# LightingUPS.net
KiCad netlist of a schematic drawn in EAGLE
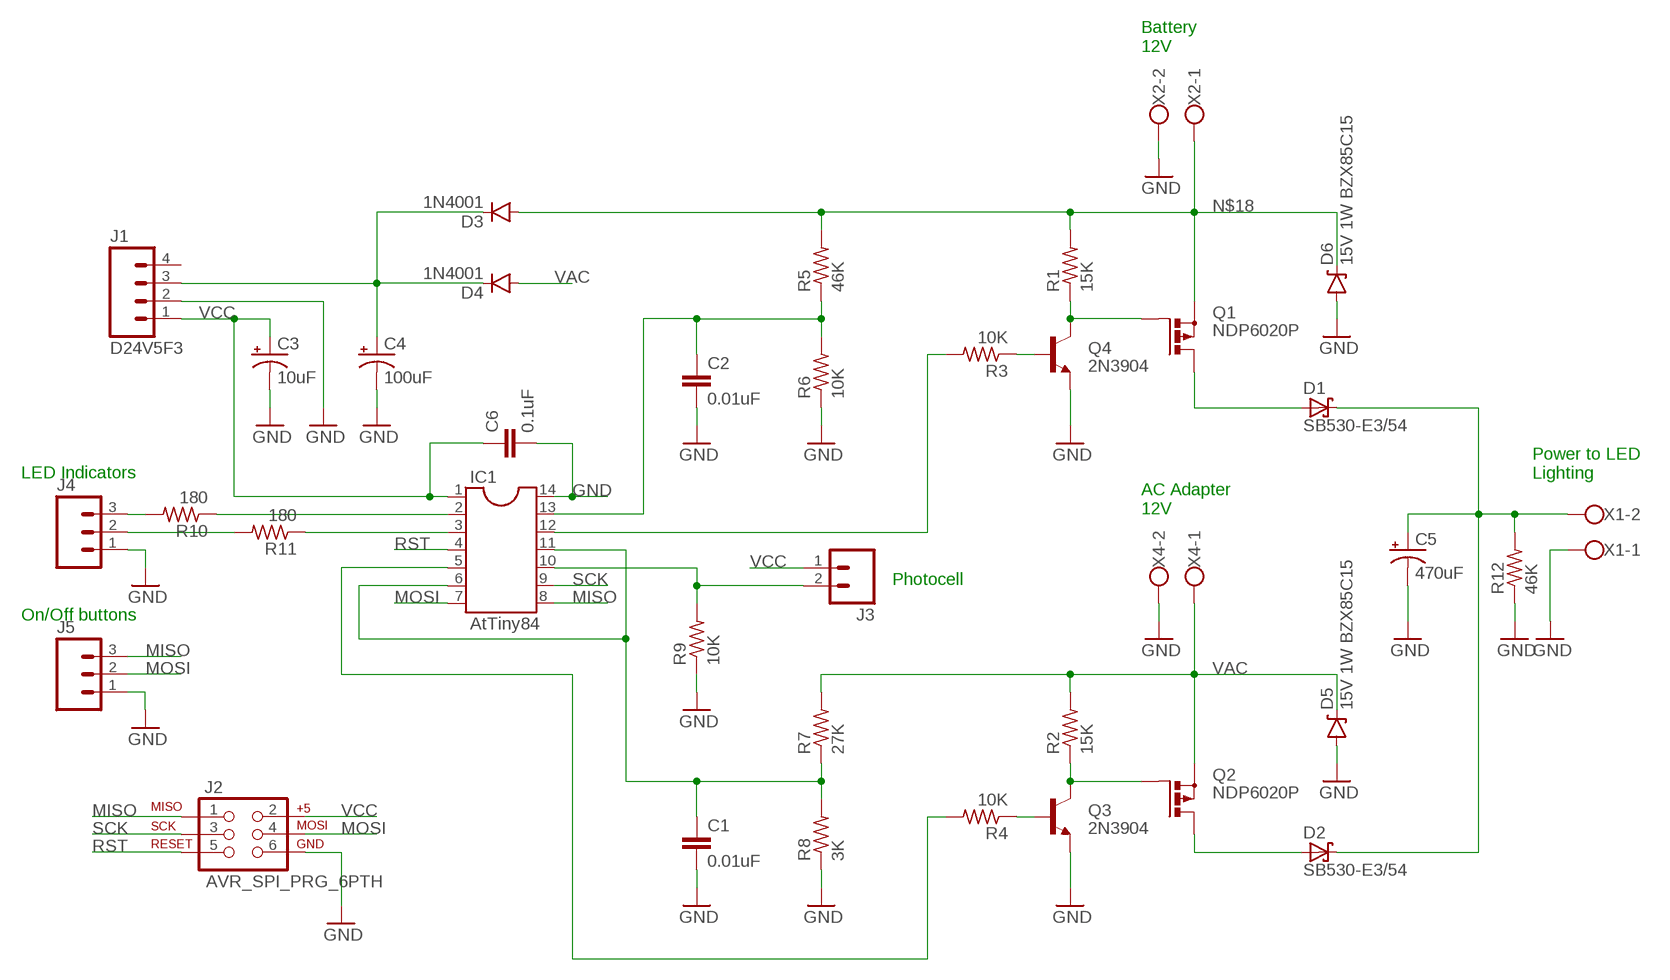
[diagram p0: schematic, sheet 1]

(export (version "E")
  (design (tool "Eeschema 10.0.6"))
  (components
    (comp (ref "C1")
      (value "0.01uF")
      (footprint "eagle-import:CAP-PTH-5MM")
      (libsource (lib "eagle-import") (part "SparkFun-Passives_CAPPTH1"))
    )
    (comp (ref "C2")
      (value "0.01uF")
      (footprint "eagle-import:CAP-PTH-5MM")
      (libsource (lib "eagle-import") (part "SparkFun-Passives_CAPPTH1"))
    )
    (comp (ref "C3")
      (value "10uF")
      (footprint "eagle-import:CPOL-RADIAL-100UF-25V")
      (libsource (lib "eagle-import") (part "CAP_POLPTH1"))
    )
    (comp (ref "C4")
      (value "100uF")
      (footprint "eagle-import:CPOL-RADIAL-100UF-25V")
      (libsource (lib "eagle-import") (part "CAP_POLPTH1"))
    )
    (comp (ref "C5")
      (value "470uF")
      (footprint "eagle-import:CPOL-RADIAL-1000UF-25V")
      (libsource (lib "eagle-import") (part "CAP_POLPTH4"))
    )
    (comp (ref "C6")
      (value "0.1uF")
      (footprint "eagle-import:CAP-PTH-SMALL")
      (libsource (lib "eagle-import") (part "CAPPTH"))
    )
    (comp (ref "D1")
      (value "SB530-E3/54")
      (footprint "eagle-import:DO201T15")
      (libsource (lib "eagle-import") (part "SCHOTTKY-DIODEDO201T15"))
    )
    (comp (ref "D2")
      (value "SB530-E3/54")
      (footprint "eagle-import:DO201T15")
      (libsource (lib "eagle-import") (part "SCHOTTKY-DIODEDO201T15"))
    )
    (comp (ref "D3")
      (value "1N4001")
      (footprint "eagle-import:DIODE-1N4001")
      (libsource (lib "eagle-import") (part "DIODEPTH"))
    )
    (comp (ref "D4")
      (value "1N4001")
      (footprint "eagle-import:DIODE-1N4001")
      (libsource (lib "eagle-import") (part "DIODEPTH"))
    )
    (comp (ref "D5")
      (value "15V 1W BZX85C15")
      (footprint "eagle-import:DIODE-ZENER")
      (libsource (lib "eagle-import") (part "DIODE-ZENERPTH"))
    )
    (comp (ref "D6")
      (value "15V 1W BZX85C15")
      (footprint "eagle-import:DIODE-ZENER")
      (libsource (lib "eagle-import") (part "DIODE-ZENERPTH"))
    )
    (comp (ref "IC1")
      (value "AtTiny84")
      (footprint "eagle-import:DIL14")
      (libsource (lib "eagle-import") (part "DIL14"))
    )
    (comp (ref "J1")
      (value "D24V5F3")
      (footprint "eagle-import:1X04")
      (libsource (lib "eagle-import") (part "M04PTH"))
    )
    (comp (ref "J2")
      (value "AVR_SPI_PRG_6PTH")
      (footprint "eagle-import:2X3")
      (libsource (lib "eagle-import") (part "AVR_SPI_PRG_6PTH"))
    )
    (comp (ref "J3")
      (value "M02PTH")
      (footprint "eagle-import:1X02")
      (libsource (lib "eagle-import") (part "M02PTH"))
    )
    (comp (ref "J4")
      (value "M03PTH")
      (footprint "eagle-import:1X03")
      (libsource (lib "eagle-import") (part "M03PTH"))
    )
    (comp (ref "J5")
      (value "M03PTH")
      (footprint "eagle-import:1X03")
      (libsource (lib "eagle-import") (part "M03PTH"))
    )
    (comp (ref "Q1")
      (value "NDP6020P")
      (footprint "eagle-import:TO220BV")
      (libsource (lib "eagle-import") (part "PMOSFET_PTO220BV"))
    )
    (comp (ref "Q2")
      (value "NDP6020P")
      (footprint "eagle-import:TO220BV")
      (libsource (lib "eagle-import") (part "PMOSFET_PTO220BV"))
    )
    (comp (ref "Q3")
      (value "2N3904")
      (footprint "eagle-import:TO-92-AMMO")
      (libsource (lib "eagle-import") (part "TRANSISTOR_NPNTO-92-AMMO"))
    )
    (comp (ref "Q4")
      (value "2N3904")
      (footprint "eagle-import:TO-92-AMMO")
      (libsource (lib "eagle-import") (part "TRANSISTOR_NPNTO-92-AMMO"))
    )
    (comp (ref "R1")
      (value "15K")
      (footprint "eagle-import:0204_5")
      (libsource (lib "eagle-import") (part "R-US_0204/5"))
    )
    (comp (ref "R2")
      (value "15K")
      (footprint "eagle-import:0204_5")
      (libsource (lib "eagle-import") (part "R-US_0204/5"))
    )
    (comp (ref "R3")
      (value "10K")
      (footprint "eagle-import:0204_5")
      (libsource (lib "eagle-import") (part "R-US_0204/5"))
    )
    (comp (ref "R4")
      (value "10K")
      (footprint "eagle-import:0204_5")
      (libsource (lib "eagle-import") (part "R-US_0204/5"))
    )
    (comp (ref "R5")
      (value "46K")
      (footprint "eagle-import:0204_5")
      (libsource (lib "eagle-import") (part "R-US_0204/5"))
    )
    (comp (ref "R6")
      (value "10K")
      (footprint "eagle-import:0204_5")
      (libsource (lib "eagle-import") (part "R-US_0204/5"))
    )
    (comp (ref "R7")
      (value "27K")
      (footprint "eagle-import:0204_5")
      (libsource (lib "eagle-import") (part "R-US_0204/5"))
    )
    (comp (ref "R8")
      (value "3K")
      (footprint "eagle-import:0204_5")
      (libsource (lib "eagle-import") (part "R-US_0204/5"))
    )
    (comp (ref "R9")
      (value "10K")
      (footprint "eagle-import:0204_5")
      (libsource (lib "eagle-import") (part "R-US_0204/5"))
    )
    (comp (ref "R10")
      (value "180")
      (footprint "eagle-import:0204_5")
      (libsource (lib "eagle-import") (part "R-US_0204/5"))
    )
    (comp (ref "R11")
      (value "180")
      (footprint "eagle-import:0204_5")
      (libsource (lib "eagle-import") (part "R-US_0204/5"))
    )
    (comp (ref "R12")
      (value "46K")
      (footprint "eagle-import:0204_5")
      (libsource (lib "eagle-import") (part "R-US_0204/5"))
    )
    (comp (ref "X1")
      (value "W237-102")
      (footprint "eagle-import:W237-102")
      (fields (field (name "MPN") "237-102"))
      (libsource (lib "eagle-import") (part "W237-102"))
    )
    (comp (ref "X2")
      (value "W237-102")
      (footprint "eagle-import:W237-102")
      (fields (field (name "MPN") "237-102"))
      (libsource (lib "eagle-import") (part "W237-102"))
    )
    (comp (ref "X4")
      (value "W237-102")
      (footprint "eagle-import:W237-102")
      (fields (field (name "MPN") "237-102"))
      (libsource (lib "eagle-import") (part "W237-102"))
    )
  )
  (nets
    (net (code "1") (name "/MISO") (class "Default")
      (node (ref "IC1") (pin "8") (pinfunction "8_8") (pintype "passive"))
      (node (ref "J2") (pin "1") (pinfunction "1_1") (pintype "passive"))
      (node (ref "J5") (pin "3") (pinfunction "3_3") (pintype "passive"))
    )
    (net (code "2") (name "/MOSI") (class "Default")
      (node (ref "IC1") (pin "7") (pinfunction "7_7") (pintype "passive"))
      (node (ref "J2") (pin "4") (pinfunction "4_4") (pintype "passive"))
      (node (ref "J5") (pin "2") (pinfunction "2_2") (pintype "passive"))
    )
    (net (code "3") (name "/N$18") (class "Default")
      (node (ref "D3") (pin "A") (pinfunction "A_A") (pintype "passive"))
      (node (ref "D6") (pin "P$1") (pinfunction "C_P$1") (pintype "passive"))
      (node (ref "Q1") (pin "S") (pinfunction "S_S") (pintype "passive"))
      (node (ref "R1") (pin "2") (pinfunction "2_2") (pintype "passive"))
      (node (ref "R5") (pin "2") (pinfunction "2_2") (pintype "passive"))
      (node (ref "X2") (pin "1") (pinfunction "KL_1") (pintype "passive"))
    )
    (net (code "4") (name "/RST") (class "Default")
      (node (ref "IC1") (pin "4") (pinfunction "4_4") (pintype "passive"))
      (node (ref "J2") (pin "5") (pinfunction "5_5") (pintype "passive"))
    )
    (net (code "5") (name "/SCK") (class "Default")
      (node (ref "IC1") (pin "9") (pinfunction "9_9") (pintype "passive"))
      (node (ref "J2") (pin "3") (pinfunction "3_3") (pintype "passive"))
    )
    (net (code "6") (name "/VAC") (class "Default")
      (node (ref "D4") (pin "A") (pinfunction "A_A") (pintype "passive"))
      (node (ref "D5") (pin "P$1") (pinfunction "C_P$1") (pintype "passive"))
      (node (ref "Q2") (pin "S") (pinfunction "S_S") (pintype "passive"))
      (node (ref "R2") (pin "2") (pinfunction "2_2") (pintype "passive"))
      (node (ref "R7") (pin "2") (pinfunction "2_2") (pintype "passive"))
      (node (ref "X4") (pin "1") (pinfunction "KL_1") (pintype "passive"))
    )
    (net (code "7") (name "/VCC") (class "Default")
      (node (ref "C3") (pin "1") (pinfunction "+_1") (pintype "passive"))
      (node (ref "C6") (pin "1") (pinfunction "1_1") (pintype "passive"))
      (node (ref "IC1") (pin "1") (pinfunction "1_1") (pintype "passive"))
      (node (ref "J1") (pin "1") (pinfunction "1_1") (pintype "passive"))
      (node (ref "J2") (pin "2") (pinfunction "2_2") (pintype "passive"))
      (node (ref "J3") (pin "1") (pinfunction "1_1") (pintype "passive"))
    )
    (net (code "8") (name "GND") (class "Default")
      (node (ref "C1") (pin "2") (pinfunction "2_2") (pintype "passive"))
      (node (ref "C2") (pin "2") (pinfunction "2_2") (pintype "passive"))
      (node (ref "C3") (pin "2") (pinfunction "-_2") (pintype "passive"))
      (node (ref "C4") (pin "2") (pinfunction "-_2") (pintype "passive"))
      (node (ref "C5") (pin "-") (pinfunction "-_-") (pintype "passive"))
      (node (ref "C6") (pin "2") (pinfunction "2_2") (pintype "passive"))
      (node (ref "D5") (pin "P$2") (pinfunction "A_P$2") (pintype "passive"))
      (node (ref "D6") (pin "P$2") (pinfunction "A_P$2") (pintype "passive"))
      (node (ref "IC1") (pin "14") (pinfunction "14_14") (pintype "passive"))
      (node (ref "J1") (pin "2") (pinfunction "2_2") (pintype "passive"))
      (node (ref "J2") (pin "6") (pinfunction "6_6") (pintype "passive"))
      (node (ref "J4") (pin "1") (pinfunction "1_1") (pintype "passive"))
      (node (ref "J5") (pin "1") (pinfunction "1_1") (pintype "passive"))
      (node (ref "Q3") (pin "1") (pinfunction "E_1") (pintype "passive"))
      (node (ref "Q4") (pin "1") (pinfunction "E_1") (pintype "passive"))
      (node (ref "R12") (pin "1") (pinfunction "1_1") (pintype "passive"))
      (node (ref "R6") (pin "1") (pinfunction "1_1") (pintype "passive"))
      (node (ref "R8") (pin "1") (pinfunction "1_1") (pintype "passive"))
      (node (ref "R9") (pin "1") (pinfunction "1_1") (pintype "passive"))
      (node (ref "X1") (pin "1") (pinfunction "KL_1") (pintype "passive"))
      (node (ref "X2") (pin "2") (pinfunction "KL_2") (pintype "passive"))
      (node (ref "X4") (pin "2") (pinfunction "KL_2") (pintype "passive"))
    )
    (net (code "9") (name "Net-(C1-Pad1)") (class "Default")
      (node (ref "C1") (pin "1") (pinfunction "1_1") (pintype "passive"))
      (node (ref "IC1") (pin "11") (pinfunction "11_11") (pintype "passive"))
      (node (ref "IC1") (pin "6") (pinfunction "6_6") (pintype "passive"))
      (node (ref "R7") (pin "1") (pinfunction "1_1") (pintype "passive"))
      (node (ref "R8") (pin "2") (pinfunction "2_2") (pintype "passive"))
    )
    (net (code "10") (name "Net-(C2-Pad1)") (class "Default")
      (node (ref "C2") (pin "1") (pinfunction "1_1") (pintype "passive"))
      (node (ref "IC1") (pin "13") (pinfunction "13_13") (pintype "passive"))
      (node (ref "R5") (pin "1") (pinfunction "1_1") (pintype "passive"))
      (node (ref "R6") (pin "2") (pinfunction "2_2") (pintype "passive"))
    )
    (net (code "11") (name "Net-(C4-+)") (class "Default")
      (node (ref "C4") (pin "1") (pinfunction "+_1") (pintype "passive"))
      (node (ref "D3") (pin "C") (pinfunction "C_C") (pintype "passive"))
      (node (ref "D4") (pin "C") (pinfunction "C_C") (pintype "passive"))
      (node (ref "J1") (pin "3") (pinfunction "3_3") (pintype "passive"))
    )
    (net (code "12") (name "Net-(D1-PadA)") (class "Default")
      (node (ref "D1") (pin "A") (pinfunction "A_A") (pintype "passive"))
      (node (ref "Q1") (pin "D") (pinfunction "D_D") (pintype "passive"))
    )
    (net (code "13") (name "Net-(D2-PadA)") (class "Default")
      (node (ref "D2") (pin "A") (pinfunction "A_A") (pintype "passive"))
      (node (ref "Q2") (pin "D") (pinfunction "D_D") (pintype "passive"))
    )
    (net (code "14") (name "Net-(IC1-Pad2)") (class "Default")
      (node (ref "IC1") (pin "2") (pinfunction "2_2") (pintype "passive"))
      (node (ref "R10") (pin "1") (pinfunction "1_1") (pintype "passive"))
    )
    (net (code "15") (name "Net-(IC1-Pad3)") (class "Default")
      (node (ref "IC1") (pin "3") (pinfunction "3_3") (pintype "passive"))
      (node (ref "R11") (pin "1") (pinfunction "1_1") (pintype "passive"))
    )
    (net (code "16") (name "Net-(IC1-Pad5)") (class "Default")
      (node (ref "IC1") (pin "5") (pinfunction "5_5") (pintype "passive"))
      (node (ref "R4") (pin "2") (pinfunction "2_2") (pintype "passive"))
    )
    (net (code "17") (name "Net-(IC1-Pad10)") (class "Default")
      (node (ref "IC1") (pin "10") (pinfunction "10_10") (pintype "passive"))
      (node (ref "J3") (pin "2") (pinfunction "2_2") (pintype "passive"))
      (node (ref "R9") (pin "2") (pinfunction "2_2") (pintype "passive"))
    )
    (net (code "18") (name "Net-(IC1-Pad12)") (class "Default")
      (node (ref "IC1") (pin "12") (pinfunction "12_12") (pintype "passive"))
      (node (ref "R3") (pin "2") (pinfunction "2_2") (pintype "passive"))
    )
    (net (code "19") (name "Net-(J4-Pad2)") (class "Default")
      (node (ref "J4") (pin "2") (pinfunction "2_2") (pintype "passive"))
      (node (ref "R11") (pin "2") (pinfunction "2_2") (pintype "passive"))
    )
    (net (code "20") (name "Net-(J4-Pad3)") (class "Default")
      (node (ref "J4") (pin "3") (pinfunction "3_3") (pintype "passive"))
      (node (ref "R10") (pin "2") (pinfunction "2_2") (pintype "passive"))
    )
    (net (code "21") (name "Net-(Q3-B)") (class "Default")
      (node (ref "Q3") (pin "2") (pinfunction "B_2") (pintype "passive"))
      (node (ref "R4") (pin "1") (pinfunction "1_1") (pintype "passive"))
    )
    (net (code "22") (name "Net-(Q3-C)") (class "Default")
      (node (ref "Q2") (pin "G") (pinfunction "G_G") (pintype "passive"))
      (node (ref "Q3") (pin "3") (pinfunction "C_3") (pintype "passive"))
      (node (ref "R2") (pin "1") (pinfunction "1_1") (pintype "passive"))
    )
    (net (code "23") (name "Net-(Q4-B)") (class "Default")
      (node (ref "Q4") (pin "2") (pinfunction "B_2") (pintype "passive"))
      (node (ref "R3") (pin "1") (pinfunction "1_1") (pintype "passive"))
    )
    (net (code "24") (name "Net-(Q4-C)") (class "Default")
      (node (ref "Q1") (pin "G") (pinfunction "G_G") (pintype "passive"))
      (node (ref "Q4") (pin "3") (pinfunction "C_3") (pintype "passive"))
      (node (ref "R1") (pin "1") (pinfunction "1_1") (pintype "passive"))
    )
    (net (code "25") (name "Net-(X1B-KL)") (class "Default")
      (node (ref "C5") (pin "+") (pinfunction "+_+") (pintype "passive"))
      (node (ref "D1") (pin "C") (pinfunction "C_C") (pintype "passive"))
      (node (ref "D2") (pin "C") (pinfunction "C_C") (pintype "passive"))
      (node (ref "R12") (pin "2") (pinfunction "2_2") (pintype "passive"))
      (node (ref "X1") (pin "2") (pinfunction "KL_2") (pintype "passive"))
    )
    (net (code "26") (name "unconnected-(J1-Pad4)") (class "Default")
      (node (ref "J1") (pin "4") (pinfunction "4_4") (pintype "passive"))
    )
  )
)
